# HS_LED_CONTROLLER_V1.net
KiCad netlist of a schematic drawn in EAGLE
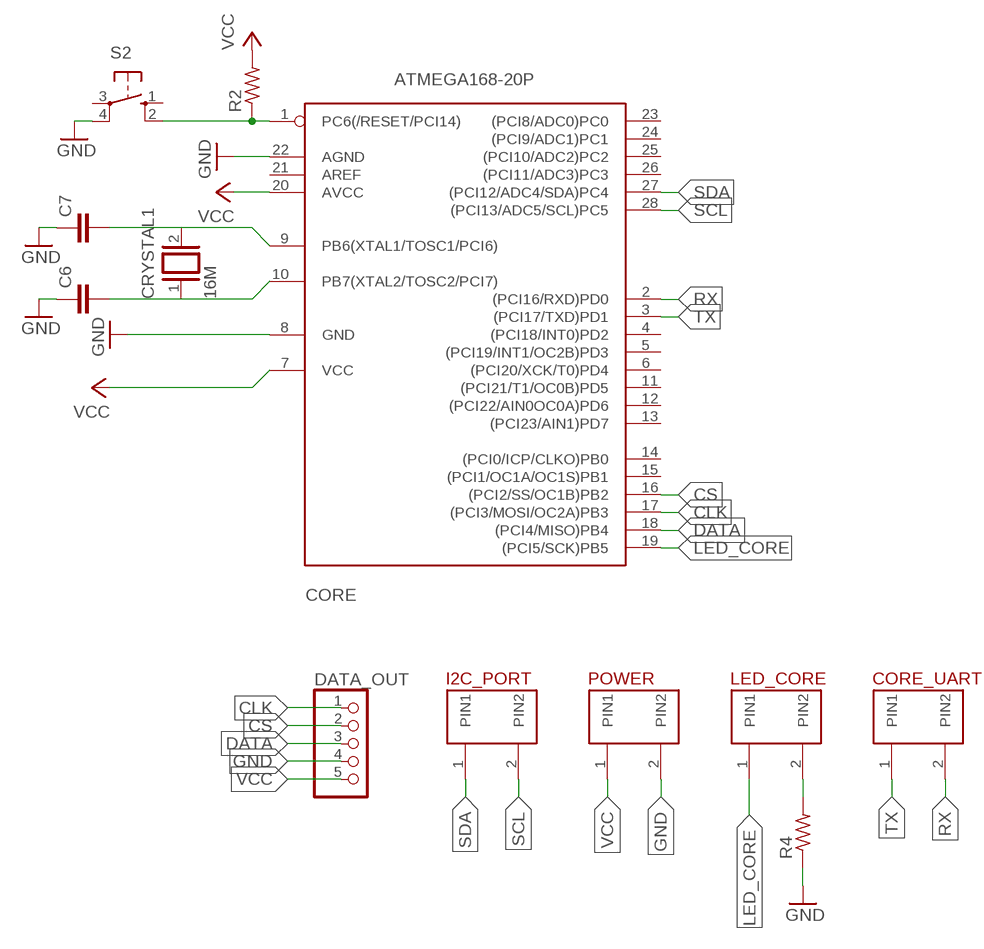
[diagram p0: schematic, sheet 1]

(export (version "E")
  (design (tool "Eeschema 10.0.6"))
  (components
    (comp (ref "C6")
      (value "C-EU025-024X044")
      (footprint "eagle-import:C025-024X044")
      (libsource (lib "eagle-import") (part "C-EU025-024X044"))
    )
    (comp (ref "C7")
      (value "C-EU025-024X044")
      (footprint "eagle-import:C025-024X044")
      (libsource (lib "eagle-import") (part "C-EU025-024X044"))
    )
    (comp (ref "CORE")
      (value "ATMEGA168-20P")
      (footprint "eagle-import:DIL28-3")
      (libsource (lib "eagle-import") (part "ATMEGA168P-20"))
    )
    (comp (ref "CORE_UART")
      (value "7325")
      (footprint "eagle-import:2.54MM")
      (libsource (lib "eagle-import") (part "7325"))
    )
    (comp (ref "CRYSTAL1")
      (value "16M")
      (footprint "eagle-import:QS")
      (libsource (lib "eagle-import") (part "XTAL/S"))
    )
    (comp (ref "DATA_OUT")
      (value "PINHD-1X5/90")
      (footprint "eagle-import:1X05_90")
      (libsource (lib "eagle-import") (part "PINHD-1X5/90"))
    )
    (comp (ref "I2C_PORT")
      (value "7325")
      (footprint "eagle-import:2.54MM")
      (libsource (lib "eagle-import") (part "7325"))
    )
    (comp (ref "LED_CORE")
      (value "7325")
      (footprint "eagle-import:2.54MM")
      (libsource (lib "eagle-import") (part "7325"))
    )
    (comp (ref "POWER")
      (value "7325")
      (footprint "eagle-import:2.54MM")
      (libsource (lib "eagle-import") (part "7325"))
    )
    (comp (ref "R2")
      (value "R-US_0207/10")
      (footprint "eagle-import:0207_10")
      (libsource (lib "eagle-import") (part "R-US_0207/10"))
    )
    (comp (ref "R4")
      (value "R-US_0207/10")
      (footprint "eagle-import:0207_10")
      (libsource (lib "eagle-import") (part "R-US_0207/10"))
    )
    (comp (ref "S2")
      (value "10-XX")
      (footprint "eagle-import:B3F-10XX")
      (fields (field (name "MPN") "B3F-1000"))
      (libsource (lib "eagle-import") (part "10-XX"))
    )
  )
  (nets
    (net (code "1") (name "CLK") (class "Default")
      (node (ref "CORE") (pin "17") (pinfunction "(PCI3/MOSI/OC2A)PB3_17") (pintype "bidirectional"))
      (node (ref "DATA_OUT") (pin "1") (pinfunction "1_1") (pintype "passive"))
    )
    (net (code "2") (name "CS") (class "Default")
      (node (ref "CORE") (pin "16") (pinfunction "(PCI2/SS/OC1B)PB2_16") (pintype "bidirectional"))
      (node (ref "DATA_OUT") (pin "2") (pinfunction "2_2") (pintype "passive"))
    )
    (net (code "3") (name "DATA") (class "Default")
      (node (ref "CORE") (pin "18") (pinfunction "(PCI4/MISO)PB4_18") (pintype "bidirectional"))
      (node (ref "DATA_OUT") (pin "3") (pinfunction "3_3") (pintype "passive"))
    )
    (net (code "4") (name "GND") (class "Default")
      (node (ref "C6") (pin "1") (pinfunction "1_1") (pintype "passive"))
      (node (ref "C7") (pin "1") (pinfunction "1_1") (pintype "passive"))
      (node (ref "CORE") (pin "22") (pinfunction "AGND_22") (pintype "bidirectional"))
      (node (ref "CORE") (pin "8") (pinfunction "GND_8") (pintype "bidirectional"))
      (node (ref "DATA_OUT") (pin "4") (pinfunction "4_4") (pintype "passive"))
      (node (ref "POWER") (pin "2") (pinfunction "PIN2_2") (pintype "bidirectional"))
      (node (ref "R4") (pin "1") (pinfunction "1_1") (pintype "passive"))
      (node (ref "S2") (pin "4") (pinfunction "P1_4") (pintype "passive"))
    )
    (net (code "5") (name "LED_CORE") (class "Default")
      (node (ref "CORE") (pin "19") (pinfunction "(PCI5/SCK)PB5_19") (pintype "bidirectional"))
      (node (ref "LED_CORE") (pin "1") (pinfunction "PIN1_1") (pintype "bidirectional"))
    )
    (net (code "6") (name "Net-(CORE-PB6(XTAL1{slash}TOSC1{slash}PCI6))") (class "Default")
      (node (ref "C7") (pin "2") (pinfunction "2_2") (pintype "passive"))
      (node (ref "CORE") (pin "9") (pinfunction "PB6(XTAL1/TOSC1/PCI6)_9") (pintype "bidirectional"))
      (node (ref "CRYSTAL1") (pin "2") (pinfunction "2_2") (pintype "passive"))
    )
    (net (code "7") (name "Net-(CORE-PB7(XTAL2{slash}TOSC2{slash}PCI7))") (class "Default")
      (node (ref "C6") (pin "2") (pinfunction "2_2") (pintype "passive"))
      (node (ref "CORE") (pin "10") (pinfunction "PB7(XTAL2/TOSC2/PCI7)_10") (pintype "bidirectional"))
      (node (ref "CRYSTAL1") (pin "1") (pinfunction "1_1") (pintype "passive"))
    )
    (net (code "8") (name "Net-(CORE-PC6({slash}RESET{slash}PCI14))") (class "Default")
      (node (ref "CORE") (pin "1") (pinfunction "PC6(/RESET/PCI14)_1") (pintype "bidirectional"))
      (node (ref "R2") (pin "1") (pinfunction "1_1") (pintype "passive"))
      (node (ref "S2") (pin "2") (pinfunction "S1_2") (pintype "passive"))
    )
    (net (code "9") (name "Net-(LED_CORE-PIN2)") (class "Default")
      (node (ref "LED_CORE") (pin "2") (pinfunction "PIN2_2") (pintype "bidirectional"))
      (node (ref "R4") (pin "2") (pinfunction "2_2") (pintype "passive"))
    )
    (net (code "10") (name "RX") (class "Default")
      (node (ref "CORE") (pin "2") (pinfunction "(PCI16/RXD)PD0_2") (pintype "bidirectional"))
      (node (ref "CORE_UART") (pin "2") (pinfunction "PIN2_2") (pintype "bidirectional"))
    )
    (net (code "11") (name "SCL") (class "Default")
      (node (ref "CORE") (pin "28") (pinfunction "(PCI13/ADC5/SCL)PC5_28") (pintype "bidirectional"))
      (node (ref "I2C_PORT") (pin "2") (pinfunction "PIN2_2") (pintype "bidirectional"))
    )
    (net (code "12") (name "SDA") (class "Default")
      (node (ref "CORE") (pin "27") (pinfunction "(PCI12/ADC4/SDA)PC4_27") (pintype "bidirectional"))
      (node (ref "I2C_PORT") (pin "1") (pinfunction "PIN1_1") (pintype "bidirectional"))
    )
    (net (code "13") (name "TX") (class "Default")
      (node (ref "CORE") (pin "3") (pinfunction "(PCI17/TXD)PD1_3") (pintype "bidirectional"))
      (node (ref "CORE_UART") (pin "1") (pinfunction "PIN1_1") (pintype "bidirectional"))
    )
    (net (code "14") (name "VCC") (class "Default")
      (node (ref "CORE") (pin "20") (pinfunction "AVCC_20") (pintype "bidirectional"))
      (node (ref "CORE") (pin "7") (pinfunction "VCC_7") (pintype "bidirectional"))
      (node (ref "DATA_OUT") (pin "5") (pinfunction "5_5") (pintype "passive"))
      (node (ref "POWER") (pin "1") (pinfunction "PIN1_1") (pintype "bidirectional"))
      (node (ref "R2") (pin "2") (pinfunction "2_2") (pintype "passive"))
    )
    (net (code "15") (name "unconnected-(CORE-(PCI0{slash}ICP{slash}CLKO)PB0-Pad14)") (class "Default")
      (node (ref "CORE") (pin "14") (pinfunction "(PCI0/ICP/CLKO)PB0_14") (pintype "bidirectional"))
    )
    (net (code "16") (name "unconnected-(CORE-(PCI1{slash}OC1A{slash}OC1S)PB1-Pad15)") (class "Default")
      (node (ref "CORE") (pin "15") (pinfunction "(PCI1/OC1A/OC1S)PB1_15") (pintype "bidirectional"))
    )
    (net (code "17") (name "unconnected-(CORE-(PCI8{slash}ADC0)PC0-Pad23)") (class "Default")
      (node (ref "CORE") (pin "23") (pinfunction "(PCI8/ADC0)PC0_23") (pintype "bidirectional"))
    )
    (net (code "18") (name "unconnected-(CORE-(PCI9{slash}ADC1)PC1-Pad24)") (class "Default")
      (node (ref "CORE") (pin "24") (pinfunction "(PCI9/ADC1)PC1_24") (pintype "bidirectional"))
    )
    (net (code "19") (name "unconnected-(CORE-(PCI10{slash}ADC2)PC2-Pad25)") (class "Default")
      (node (ref "CORE") (pin "25") (pinfunction "(PCI10/ADC2)PC2_25") (pintype "bidirectional"))
    )
    (net (code "20") (name "unconnected-(CORE-(PCI11{slash}ADC3)PC3-Pad26)") (class "Default")
      (node (ref "CORE") (pin "26") (pinfunction "(PCI11/ADC3)PC3_26") (pintype "bidirectional"))
    )
    (net (code "21") (name "unconnected-(CORE-(PCI18{slash}INT0)PD2-Pad4)") (class "Default")
      (node (ref "CORE") (pin "4") (pinfunction "(PCI18/INT0)PD2_4") (pintype "bidirectional"))
    )
    (net (code "22") (name "unconnected-(CORE-(PCI19{slash}INT1{slash}OC2B)PD3-Pad5)") (class "Default")
      (node (ref "CORE") (pin "5") (pinfunction "(PCI19/INT1/OC2B)PD3_5") (pintype "bidirectional"))
    )
    (net (code "23") (name "unconnected-(CORE-(PCI20{slash}XCK{slash}T0)PD4-Pad6)") (class "Default")
      (node (ref "CORE") (pin "6") (pinfunction "(PCI20/XCK/T0)PD4_6") (pintype "bidirectional"))
    )
    (net (code "24") (name "unconnected-(CORE-(PCI21{slash}T1{slash}OC0B)PD5-Pad11)") (class "Default")
      (node (ref "CORE") (pin "11") (pinfunction "(PCI21/T1/OC0B)PD5_11") (pintype "bidirectional"))
    )
    (net (code "25") (name "unconnected-(CORE-(PCI22{slash}AIN0OC0A)PD6-Pad12)") (class "Default")
      (node (ref "CORE") (pin "12") (pinfunction "(PCI22/AIN0OC0A)PD6_12") (pintype "bidirectional"))
    )
    (net (code "26") (name "unconnected-(CORE-(PCI23{slash}AIN1)PD7-Pad13)") (class "Default")
      (node (ref "CORE") (pin "13") (pinfunction "(PCI23/AIN1)PD7_13") (pintype "bidirectional"))
    )
    (net (code "27") (name "unconnected-(CORE-AREF-Pad21)") (class "Default")
      (node (ref "CORE") (pin "21") (pinfunction "AREF_21") (pintype "bidirectional"))
    )
    (net (code "28") (name "unconnected-(S2-P-Pad3)") (class "Default")
      (node (ref "S2") (pin "3") (pinfunction "P_3") (pintype "passive"))
    )
    (net (code "29") (name "unconnected-(S2-S-Pad1)") (class "Default")
      (node (ref "S2") (pin "1") (pinfunction "S_1") (pintype "passive"))
    )
  )
)
